# illumi-motherboard.net
KiCad netlist of a schematic drawn in EAGLE
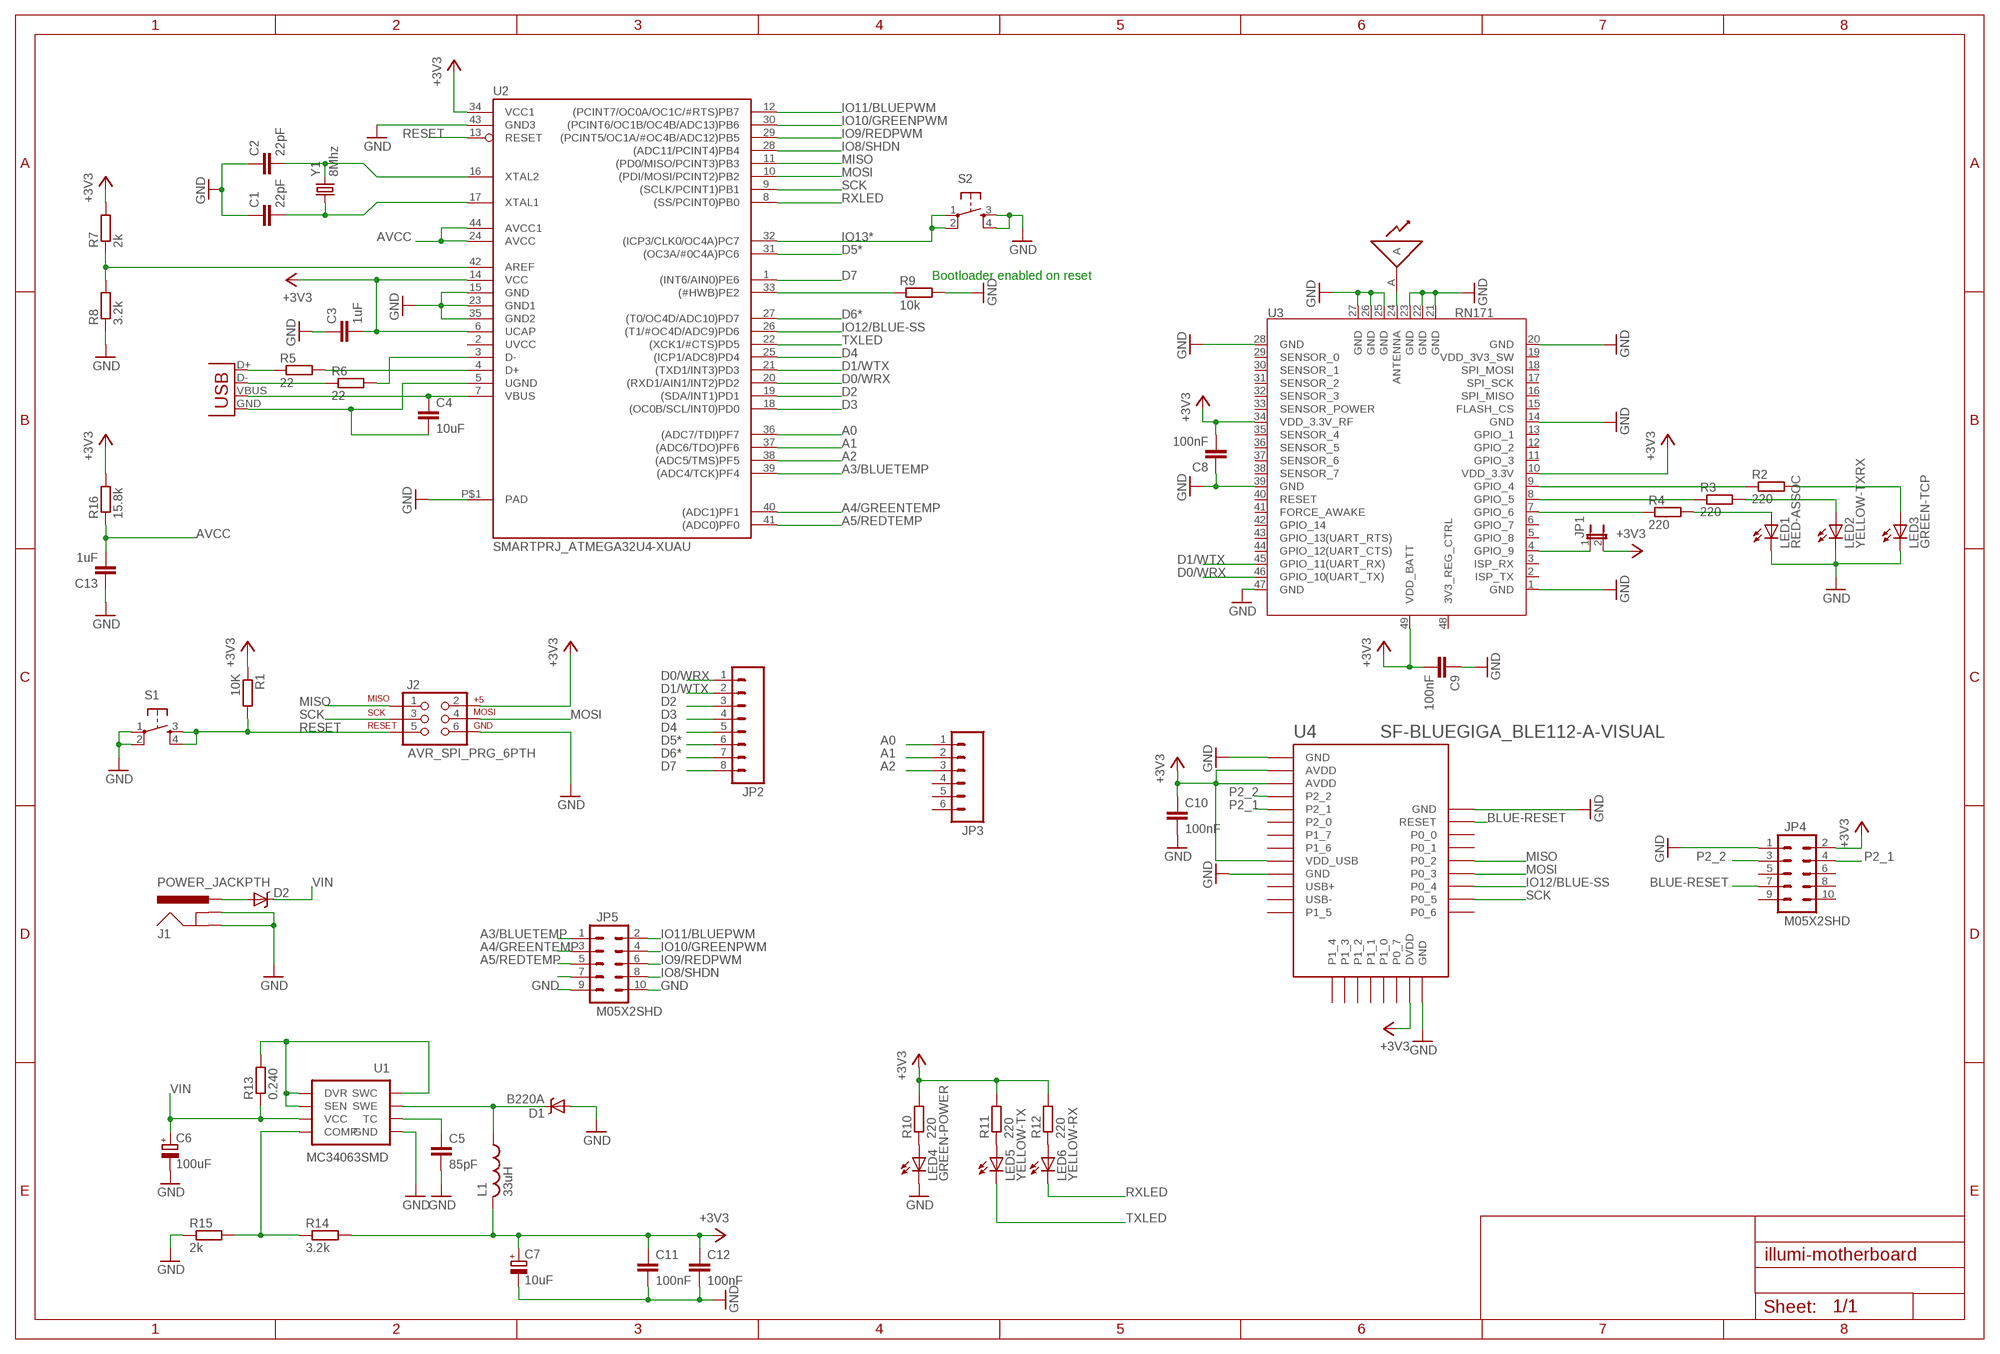
[diagram p0: schematic, sheet 1]

(export (version "E")
  (design (tool "Eeschema 10.0.6"))
  (components
    (comp (ref "A1")
      (value "ANTENNAWIRE")
      (footprint "eagle-import:ANTENNA-WIRE")
      (libsource (lib "eagle-import") (part "ANTENNAWIRE"))
    )
    (comp (ref "C1")
      (value "22pF")
      (footprint "eagle-import:C0805")
      (libsource (lib "eagle-import") (part "C-EUC0805"))
    )
    (comp (ref "C2")
      (value "22pF")
      (footprint "eagle-import:C0805")
      (libsource (lib "eagle-import") (part "C-EUC0805"))
    )
    (comp (ref "C3")
      (value "1uF")
      (footprint "eagle-import:C0805")
      (libsource (lib "eagle-import") (part "C-EUC0805"))
    )
    (comp (ref "C4")
      (value "10uF")
      (footprint "eagle-import:C0805")
      (libsource (lib "eagle-import") (part "C-EUC0805"))
    )
    (comp (ref "C5")
      (value "85pF")
      (footprint "eagle-import:C0805")
      (libsource (lib "eagle-import") (part "C-EUC0805"))
    )
    (comp (ref "C6")
      (value "100uF")
      (footprint "eagle-import:PANASONIC_D")
      (libsource (lib "eagle-import") (part "CPOL-EUD"))
    )
    (comp (ref "C7")
      (value "10uF")
      (footprint "eagle-import:SMC_C")
      (libsource (lib "eagle-import") (part "CPOL-EUSMCC"))
    )
    (comp (ref "C8")
      (value "100nF")
      (footprint "eagle-import:C0805")
      (libsource (lib "eagle-import") (part "C-EUC0805"))
    )
    (comp (ref "C9")
      (value "100nF")
      (footprint "eagle-import:C0805")
      (libsource (lib "eagle-import") (part "C-EUC0805"))
    )
    (comp (ref "C10")
      (value "100nF")
      (footprint "eagle-import:C0805")
      (libsource (lib "eagle-import") (part "C-EUC0805"))
    )
    (comp (ref "C11")
      (value "100nF")
      (footprint "eagle-import:C0805")
      (libsource (lib "eagle-import") (part "C-EUC0805"))
    )
    (comp (ref "C12")
      (value "100nF")
      (footprint "eagle-import:C0805")
      (libsource (lib "eagle-import") (part "C-EUC0805"))
    )
    (comp (ref "C13")
      (value "1uF")
      (footprint "eagle-import:C0805")
      (libsource (lib "eagle-import") (part "C-EUC0805"))
    )
    (comp (ref "D1")
      (value "B220A")
      (footprint "eagle-import:SMA-DIODE-BIG")
      (libsource (lib "eagle-import") (part "DIODE-SCHOTTKYBIGPAD"))
    )
    (comp (ref "D2")
      (value "DIODE-SCHOTTKYBIGPAD")
      (footprint "eagle-import:SMA-DIODE-BIG")
      (libsource (lib "eagle-import") (part "DIODE-SCHOTTKYBIGPAD"))
    )
    (comp (ref "J1")
      (value "POWER_JACKPTH")
      (footprint "eagle-import:POWER_JACK_PTH")
      (libsource (lib "eagle-import") (part "POWER_JACKPTH"))
    )
    (comp (ref "J2")
      (value "AVR_SPI_PRG_6PTH")
      (footprint "eagle-import:2X3")
      (libsource (lib "eagle-import") (part "AVR_SPI_PRG_6PTH"))
    )
    (comp (ref "JP1")
      (value "JUMPER-2PTH")
      (footprint "eagle-import:1X02")
      (libsource (lib "eagle-import") (part "JUMPER-2PTH"))
    )
    (comp (ref "JP2")
      (value "M081X08")
      (footprint "eagle-import:1X08")
      (libsource (lib "eagle-import") (part "M081X08"))
    )
    (comp (ref "JP3")
      (value "M06FEMALE_LOCK")
      (footprint "eagle-import:1X06_FEMALE_LOCK.010")
      (libsource (lib "eagle-import") (part "M06FEMALE_LOCK"))
    )
    (comp (ref "JP4")
      (value "M05X2SHD")
      (footprint "eagle-import:2X5-SHROUDED")
      (libsource (lib "eagle-import") (part "M05X2SHD"))
    )
    (comp (ref "JP5")
      (value "M05X2SHD")
      (footprint "eagle-import:2X5-SHROUDED")
      (libsource (lib "eagle-import") (part "M05X2SHD"))
    )
    (comp (ref "L1")
      (value "33uH")
      (footprint "eagle-import:BOURNS-6045")
      (libsource (lib "eagle-import") (part "L-USBOURNS-6045"))
    )
    (comp (ref "LED1")
      (value "RED-ASSOC")
      (footprint "eagle-import:SML0805")
      (libsource (lib "eagle-import") (part "LEDSML0805"))
    )
    (comp (ref "LED2")
      (value "YELLOW-TXRX")
      (footprint "eagle-import:SML0805")
      (libsource (lib "eagle-import") (part "LEDSML0805"))
    )
    (comp (ref "LED3")
      (value "GREEN-TCP")
      (footprint "eagle-import:SML0805")
      (libsource (lib "eagle-import") (part "LEDSML0805"))
    )
    (comp (ref "LED4")
      (value "GREEN-POWER")
      (footprint "eagle-import:SML0805")
      (libsource (lib "eagle-import") (part "LEDSML0805"))
    )
    (comp (ref "LED5")
      (value "YELLOW-TX")
      (footprint "eagle-import:SML0805")
      (libsource (lib "eagle-import") (part "LEDSML0805"))
    )
    (comp (ref "LED6")
      (value "YELLOW-RX")
      (footprint "eagle-import:SML0805")
      (libsource (lib "eagle-import") (part "LEDSML0805"))
    )
    (comp (ref "R1")
      (value "10K")
      (footprint "eagle-import:R0805")
      (libsource (lib "eagle-import") (part "R-EU_R0805"))
    )
    (comp (ref "R2")
      (value "220")
      (footprint "eagle-import:R0805")
      (libsource (lib "eagle-import") (part "R-EU_R0805"))
    )
    (comp (ref "R3")
      (value "220")
      (footprint "eagle-import:R0805")
      (libsource (lib "eagle-import") (part "R-EU_R0805"))
    )
    (comp (ref "R4")
      (value "220")
      (footprint "eagle-import:R0805")
      (libsource (lib "eagle-import") (part "R-EU_R0805"))
    )
    (comp (ref "R5")
      (value "22")
      (footprint "eagle-import:R0805")
      (libsource (lib "eagle-import") (part "R-EU_R0805"))
    )
    (comp (ref "R6")
      (value "22")
      (footprint "eagle-import:R0805")
      (libsource (lib "eagle-import") (part "R-EU_R0805"))
    )
    (comp (ref "R7")
      (value "2k")
      (footprint "eagle-import:R0805")
      (libsource (lib "eagle-import") (part "R-EU_R0805"))
    )
    (comp (ref "R8")
      (value "3.2k")
      (footprint "eagle-import:R0805")
      (libsource (lib "eagle-import") (part "R-EU_R0805"))
    )
    (comp (ref "R9")
      (value "10k")
      (footprint "eagle-import:R0805")
      (libsource (lib "eagle-import") (part "resistor_R-EU_R0805"))
    )
    (comp (ref "R10")
      (value "220")
      (footprint "eagle-import:R0805")
      (libsource (lib "eagle-import") (part "R-EU_R0805"))
    )
    (comp (ref "R11")
      (value "220")
      (footprint "eagle-import:R0805")
      (libsource (lib "eagle-import") (part "R-EU_R0805"))
    )
    (comp (ref "R12")
      (value "220")
      (footprint "eagle-import:R0805")
      (libsource (lib "eagle-import") (part "R-EU_R0805"))
    )
    (comp (ref "R13")
      (value "0.240")
      (footprint "eagle-import:R1206")
      (libsource (lib "eagle-import") (part "R-EU_R1206"))
    )
    (comp (ref "R14")
      (value "3.2k")
      (footprint "eagle-import:R0805")
      (libsource (lib "eagle-import") (part "R-EU_R0805"))
    )
    (comp (ref "R15")
      (value "2k")
      (footprint "eagle-import:R0805")
      (libsource (lib "eagle-import") (part "R-EU_R0805"))
    )
    (comp (ref "R16")
      (value "15.8k")
      (footprint "eagle-import:R0805")
      (libsource (lib "eagle-import") (part "resistor_R-EU_R0805"))
    )
    (comp (ref "S1")
      (value "TAC_SWITCHB3FS")
      (footprint "eagle-import:OMRON-B3FS")
      (libsource (lib "eagle-import") (part "TAC_SWITCHB3FS"))
    )
    (comp (ref "S2")
      (value "TAC_SWITCHB3FS")
      (footprint "eagle-import:OMRON-B3FS")
      (libsource (lib "eagle-import") (part "TAC_SWITCHB3FS"))
    )
    (comp (ref "U1")
      (value "MC34063SMD")
      (footprint "eagle-import:SO08")
      (libsource (lib "eagle-import") (part "MC34063SMD"))
    )
    (comp (ref "U2")
      (value "SMARTPRJ_ATMEGA32U4-XUAU")
      (footprint "eagle-import:SMARTPRJ_TQFP44-PAD")
      (libsource (lib "eagle-import") (part "SMARTPRJ_ATMEGA32U4-XUAU"))
    )
    (comp (ref "U3")
      (value "RN171")
      (footprint "eagle-import:MODULE_49P-1.27-26.67X17.78")
      (libsource (lib "eagle-import") (part "MODULE_WIFI-RN-171"))
    )
    (comp (ref "U4")
      (value "SF-BLUEGIGA_BLE112-A-VISUAL")
      (footprint "eagle-import:SF-BLUEGIGA_BLE112-A")
      (libsource (lib "eagle-import") (part "SF-BLUEGIGA_BLE112-A-VISUAL"))
    )
    (comp (ref "X1")
      (value "USB-MICROB")
      (footprint "eagle-import:USB-MICROB")
      (libsource (lib "eagle-import") (part "USB-MICROB"))
    )
    (comp (ref "Y1")
      (value "8Mhz")
      (footprint "eagle-import:HC49US")
      (libsource (lib "eagle-import") (part "CRYSTALHC49US"))
    )
  )
  (nets
    (net (code "1") (name "+3V3") (class "Default")
      (node (ref "C10") (pin "1") (pinfunction "1_1") (pintype "passive"))
      (node (ref "C11") (pin "1") (pinfunction "1_1") (pintype "passive"))
      (node (ref "C12") (pin "1") (pinfunction "1_1") (pintype "passive"))
      (node (ref "C3") (pin "2") (pinfunction "2_2") (pintype "passive"))
      (node (ref "C7") (pin "+") (pinfunction "+_+") (pintype "passive"))
      (node (ref "C8") (pin "2") (pinfunction "2_2") (pintype "passive"))
      (node (ref "C9") (pin "2") (pinfunction "2_2") (pintype "passive"))
      (node (ref "J2") (pin "2") (pinfunction "2_2") (pintype "passive"))
      (node (ref "JP1") (pin "2") (pinfunction "2_2") (pintype "passive"))
      (node (ref "JP4") (pin "2") (pinfunction "2_2") (pintype "passive"))
      (node (ref "L1") (pin "P$2") (pinfunction "2_P$2") (pintype "passive"))
      (node (ref "R1") (pin "1") (pinfunction "1_1") (pintype "passive"))
      (node (ref "R10") (pin "2") (pinfunction "2_2") (pintype "passive"))
      (node (ref "R11") (pin "2") (pinfunction "2_2") (pintype "passive"))
      (node (ref "R12") (pin "2") (pinfunction "2_2") (pintype "passive"))
      (node (ref "R14") (pin "2") (pinfunction "2_2") (pintype "passive"))
      (node (ref "R16") (pin "2") (pinfunction "2_2") (pintype "passive"))
      (node (ref "R7") (pin "2") (pinfunction "2_2") (pintype "passive"))
      (node (ref "U2") (pin "14") (pinfunction "VCC_14") (pintype "power_in"))
      (node (ref "U2") (pin "34") (pinfunction "VCC1_34") (pintype "power_in"))
      (node (ref "U2") (pin "6") (pinfunction "UCAP_6") (pintype "passive"))
      (node (ref "U3") (pin "10") (pinfunction "VDD_3.3V_10") (pintype "power_in"))
      (node (ref "U3") (pin "34") (pinfunction "VDD_3.3V_RF_34") (pintype "power_in"))
      (node (ref "U3") (pin "49") (pinfunction "VDD_BATT_49") (pintype "bidirectional"))
      (node (ref "U4") (pin "AVDD1") (pinfunction "AVDD_AVDD1") (pintype "power_in"))
      (node (ref "U4") (pin "AVDD2") (pinfunction "AVDD_AVDD2") (pintype "power_in"))
      (node (ref "U4") (pin "DVDD") (pinfunction "DVDD_DVDD") (pintype "power_in"))
      (node (ref "U4") (pin "VDD_USB") (pinfunction "VDD_USB_VDD_USB") (pintype "power_in"))
    )
    (net (code "2") (name "/A0") (class "Default")
      (node (ref "JP3") (pin "1") (pinfunction "1_1") (pintype "passive"))
      (node (ref "U2") (pin "36") (pinfunction "(ADC7/TDI)PF7_36") (pintype "bidirectional"))
    )
    (net (code "3") (name "/A1") (class "Default")
      (node (ref "JP3") (pin "2") (pinfunction "2_2") (pintype "passive"))
      (node (ref "U2") (pin "37") (pinfunction "(ADC6/TDO)PF6_37") (pintype "bidirectional"))
    )
    (net (code "4") (name "/A2") (class "Default")
      (node (ref "JP3") (pin "3") (pinfunction "3_3") (pintype "passive"))
      (node (ref "U2") (pin "38") (pinfunction "(ADC5/TMS)PF5_38") (pintype "bidirectional"))
    )
    (net (code "5") (name "/A3{slash}BLUETEMP") (class "Default")
      (node (ref "JP5") (pin "1") (pinfunction "1_1") (pintype "passive"))
      (node (ref "U2") (pin "39") (pinfunction "(ADC4/TCK)PF4_39") (pintype "bidirectional"))
    )
    (net (code "6") (name "/A4{slash}GREENTEMP") (class "Default")
      (node (ref "JP5") (pin "3") (pinfunction "3_3") (pintype "passive"))
      (node (ref "U2") (pin "40") (pinfunction "(ADC1)PF1_40") (pintype "bidirectional"))
    )
    (net (code "7") (name "/A5{slash}REDTEMP") (class "Default")
      (node (ref "JP5") (pin "5") (pinfunction "5_5") (pintype "passive"))
      (node (ref "U2") (pin "41") (pinfunction "(ADC0)PF0_41") (pintype "bidirectional"))
    )
    (net (code "8") (name "/AVCC") (class "Default")
      (node (ref "C13") (pin "2") (pinfunction "2_2") (pintype "passive"))
      (node (ref "R16") (pin "1") (pinfunction "1_1") (pintype "passive"))
      (node (ref "U2") (pin "24") (pinfunction "AVCC_24") (pintype "power_in"))
      (node (ref "U2") (pin "44") (pinfunction "AVCC1_44") (pintype "power_in"))
    )
    (net (code "9") (name "/BLUE-RESET") (class "Default")
      (node (ref "JP4") (pin "7") (pinfunction "7_7") (pintype "passive"))
      (node (ref "U4") (pin "RESET") (pinfunction "RESET_RESET") (pintype "input"))
    )
    (net (code "10") (name "/D0{slash}WRX") (class "Default")
      (node (ref "JP2") (pin "1") (pinfunction "1_1") (pintype "passive"))
      (node (ref "U2") (pin "20") (pinfunction "(RXD1/AIN1/INT2)PD2_20") (pintype "bidirectional"))
      (node (ref "U3") (pin "46") (pinfunction "GPIO_10(UART_TX)_46") (pintype "bidirectional"))
    )
    (net (code "11") (name "/D1{slash}WTX") (class "Default")
      (node (ref "JP2") (pin "2") (pinfunction "2_2") (pintype "passive"))
      (node (ref "U2") (pin "21") (pinfunction "(TXD1/INT3)PD3_21") (pintype "bidirectional"))
      (node (ref "U3") (pin "45") (pinfunction "GPIO_11(UART_RX)_45") (pintype "bidirectional"))
    )
    (net (code "12") (name "/D2") (class "Default")
      (node (ref "JP2") (pin "3") (pinfunction "3_3") (pintype "passive"))
      (node (ref "U2") (pin "19") (pinfunction "(SDA/INT1)PD1_19") (pintype "bidirectional"))
    )
    (net (code "13") (name "/D3") (class "Default")
      (node (ref "JP2") (pin "4") (pinfunction "4_4") (pintype "passive"))
      (node (ref "U2") (pin "18") (pinfunction "(OC0B/SCL/INT0)PD0_18") (pintype "bidirectional"))
    )
    (net (code "14") (name "/D4") (class "Default")
      (node (ref "JP2") (pin "5") (pinfunction "5_5") (pintype "passive"))
      (node (ref "U2") (pin "25") (pinfunction "(ICP1/ADC8)PD4_25") (pintype "bidirectional"))
    )
    (net (code "15") (name "/D5*") (class "Default")
      (node (ref "JP2") (pin "6") (pinfunction "6_6") (pintype "passive"))
      (node (ref "U2") (pin "31") (pinfunction "(OC3A/#0C4A)PC6_31") (pintype "bidirectional"))
    )
    (net (code "16") (name "/D6*") (class "Default")
      (node (ref "JP2") (pin "7") (pinfunction "7_7") (pintype "passive"))
      (node (ref "U2") (pin "27") (pinfunction "(T0/OC4D/ADC10)PD7_27") (pintype "bidirectional"))
    )
    (net (code "17") (name "/D7") (class "Default")
      (node (ref "JP2") (pin "8") (pinfunction "8_8") (pintype "passive"))
      (node (ref "U2") (pin "1") (pinfunction "(INT6/AIN0)PE6_1") (pintype "bidirectional"))
    )
    (net (code "18") (name "/IO8{slash}SHDN") (class "Default")
      (node (ref "JP5") (pin "8") (pinfunction "8_8") (pintype "passive"))
      (node (ref "U2") (pin "28") (pinfunction "(ADC11/PCINT4)PB4_28") (pintype "bidirectional"))
    )
    (net (code "19") (name "/IO9{slash}REDPWM") (class "Default")
      (node (ref "JP5") (pin "6") (pinfunction "6_6") (pintype "passive"))
      (node (ref "U2") (pin "29") (pinfunction "(PCINT5/OC1A/#OC4B/ADC12)PB5_29") (pintype "bidirectional"))
    )
    (net (code "20") (name "/IO10{slash}GREENPWM") (class "Default")
      (node (ref "JP5") (pin "4") (pinfunction "4_4") (pintype "passive"))
      (node (ref "U2") (pin "30") (pinfunction "(PCINT6/OC1B/OC4B/ADC13)PB6_30") (pintype "bidirectional"))
    )
    (net (code "21") (name "/IO11{slash}BLUEPWM") (class "Default")
      (node (ref "JP5") (pin "2") (pinfunction "2_2") (pintype "passive"))
      (node (ref "U2") (pin "12") (pinfunction "(PCINT7/OC0A/OC1C/#RTS)PB7_12") (pintype "bidirectional"))
    )
    (net (code "22") (name "/IO12{slash}BLUE-SS") (class "Default")
      (node (ref "U2") (pin "26") (pinfunction "(T1/#OC4D/ADC9)PD6_26") (pintype "bidirectional"))
      (node (ref "U4") (pin "P0_4") (pinfunction "P0_4_P0_4") (pintype "bidirectional"))
    )
    (net (code "23") (name "/IO13*") (class "Default")
      (node (ref "S2") (pin "1") (pinfunction "1_1") (pintype "passive"))
      (node (ref "S2") (pin "2") (pinfunction "2_2") (pintype "passive"))
      (node (ref "U2") (pin "32") (pinfunction "(ICP3/CLK0/OC4A)PC7_32") (pintype "bidirectional"))
    )
    (net (code "24") (name "/MISO") (class "Default")
      (node (ref "J2") (pin "1") (pinfunction "1_1") (pintype "passive"))
      (node (ref "U2") (pin "11") (pinfunction "(PD0/MISO/PCINT3)PB3_11") (pintype "bidirectional"))
      (node (ref "U4") (pin "P0_2") (pinfunction "P0_2_P0_2") (pintype "bidirectional"))
    )
    (net (code "25") (name "/MOSI") (class "Default")
      (node (ref "J2") (pin "4") (pinfunction "4_4") (pintype "passive"))
      (node (ref "U2") (pin "10") (pinfunction "(PDI/MOSI/PCINT2)PB2_10") (pintype "bidirectional"))
      (node (ref "U4") (pin "P0_3") (pinfunction "P0_3_P0_3") (pintype "bidirectional"))
    )
    (net (code "26") (name "/P2_1") (class "Default")
      (node (ref "JP4") (pin "4") (pinfunction "4_4") (pintype "passive"))
      (node (ref "U4") (pin "P2_1") (pinfunction "P2_1_P2_1") (pintype "bidirectional"))
    )
    (net (code "27") (name "/P2_2") (class "Default")
      (node (ref "JP4") (pin "3") (pinfunction "3_3") (pintype "passive"))
      (node (ref "U4") (pin "P2_2") (pinfunction "P2_2_P2_2") (pintype "bidirectional"))
    )
    (net (code "28") (name "/RESET") (class "Default")
      (node (ref "J2") (pin "5") (pinfunction "5_5") (pintype "passive"))
      (node (ref "R1") (pin "2") (pinfunction "2_2") (pintype "passive"))
      (node (ref "S1") (pin "3") (pinfunction "3_3") (pintype "passive"))
      (node (ref "S1") (pin "4") (pinfunction "4_4") (pintype "passive"))
      (node (ref "U2") (pin "13") (pinfunction "RESET_13") (pintype "input"))
    )
    (net (code "29") (name "/RXLED") (class "Default")
      (node (ref "LED6") (pin "C") (pinfunction "C_C") (pintype "passive"))
      (node (ref "U2") (pin "8") (pinfunction "(SS/PCINT0)PB0_8") (pintype "bidirectional"))
    )
    (net (code "30") (name "/SCK") (class "Default")
      (node (ref "J2") (pin "3") (pinfunction "3_3") (pintype "passive"))
      (node (ref "U2") (pin "9") (pinfunction "(SCLK/PCINT1)PB1_9") (pintype "bidirectional"))
      (node (ref "U4") (pin "P0_5") (pinfunction "P0_5_P0_5") (pintype "bidirectional"))
    )
    (net (code "31") (name "/TXLED") (class "Default")
      (node (ref "LED5") (pin "C") (pinfunction "C_C") (pintype "passive"))
      (node (ref "U2") (pin "22") (pinfunction "(XCK1/#CTS)PD5_22") (pintype "bidirectional"))
    )
    (net (code "32") (name "/UVCC") (class "Default")
      (node (ref "U2") (pin "2") (pinfunction "UVCC_2") (pintype "power_in"))
    )
    (net (code "33") (name "/VIN") (class "Default")
      (node (ref "C6") (pin "+") (pinfunction "+_+") (pintype "passive"))
      (node (ref "D2") (pin "C") (pinfunction "C_C") (pintype "passive"))
      (node (ref "R13") (pin "1") (pinfunction "1_1") (pintype "passive"))
      (node (ref "U1") (pin "6") (pinfunction "VCC_6") (pintype "bidirectional"))
    )
    (net (code "34") (name "GND") (class "Default")
      (node (ref "C1") (pin "1") (pinfunction "1_1") (pintype "passive"))
      (node (ref "C10") (pin "2") (pinfunction "2_2") (pintype "passive"))
      (node (ref "C11") (pin "2") (pinfunction "2_2") (pintype "passive"))
      (node (ref "C12") (pin "2") (pinfunction "2_2") (pintype "passive"))
      (node (ref "C13") (pin "1") (pinfunction "1_1") (pintype "passive"))
      (node (ref "C2") (pin "1") (pinfunction "1_1") (pintype "passive"))
      (node (ref "C3") (pin "1") (pinfunction "1_1") (pintype "passive"))
      (node (ref "C5") (pin "2") (pinfunction "2_2") (pintype "passive"))
      (node (ref "C6") (pin "-") (pinfunction "-_-") (pintype "passive"))
      (node (ref "C7") (pin "-") (pinfunction "-_-") (pintype "passive"))
      (node (ref "C8") (pin "1") (pinfunction "1_1") (pintype "passive"))
      (node (ref "C9") (pin "1") (pinfunction "1_1") (pintype "passive"))
      (node (ref "D1") (pin "A") (pinfunction "A_A") (pintype "passive"))
      (node (ref "J1") (pin "GND") (pinfunction "GND_GND") (pintype "bidirectional"))
      (node (ref "J1") (pin "GNDBREAK") (pinfunction "GNDBREAK_GNDBREAK") (pintype "bidirectional"))
      (node (ref "J2") (pin "6") (pinfunction "6_6") (pintype "passive"))
      (node (ref "JP4") (pin "1") (pinfunction "1_1") (pintype "passive"))
      (node (ref "JP5") (pin "10") (pinfunction "10_10") (pintype "passive"))
      (node (ref "JP5") (pin "9") (pinfunction "9_9") (pintype "passive"))
      (node (ref "LED1") (pin "C") (pinfunction "C_C") (pintype "passive"))
      (node (ref "LED2") (pin "C") (pinfunction "C_C") (pintype "passive"))
      (node (ref "LED3") (pin "C") (pinfunction "C_C") (pintype "passive"))
      (node (ref "LED4") (pin "C") (pinfunction "C_C") (pintype "passive"))
      (node (ref "R15") (pin "1") (pinfunction "1_1") (pintype "passive"))
      (node (ref "R8") (pin "1") (pinfunction "1_1") (pintype "passive"))
      (node (ref "R9") (pin "2") (pinfunction "2_2") (pintype "passive"))
      (node (ref "S1") (pin "1") (pinfunction "1_1") (pintype "passive"))
      (node (ref "S1") (pin "2") (pinfunction "2_2") (pintype "passive"))
      (node (ref "S2") (pin "3") (pinfunction "3_3") (pintype "passive"))
      (node (ref "S2") (pin "4") (pinfunction "4_4") (pintype "passive"))
      (node (ref "U1") (pin "4") (pinfunction "GND_4") (pintype "bidirectional"))
      (node (ref "U2") (pin "15") (pinfunction "GND_15") (pintype "power_in"))
      (node (ref "U2") (pin "23") (pinfunction "GND1_23") (pintype "power_in"))
      (node (ref "U2") (pin "35") (pinfunction "GND2_35") (pintype "power_in"))
      (node (ref "U2") (pin "43") (pinfunction "GND3_43") (pintype "power_in"))
      (node (ref "U2") (pin "P$1") (pinfunction "PAD_P$1") (pintype "power_in"))
      (node (ref "U3") (pin "1") (pinfunction "GND_1") (pintype "power_in"))
      (node (ref "U3") (pin "14") (pinfunction "GND_14") (pintype "power_in"))
      (node (ref "U3") (pin "20") (pinfunction "GND_20") (pintype "power_in"))
      (node (ref "U3") (pin "21") (pinfunction "GND_21") (pintype "power_in"))
      (node (ref "U3") (pin "22") (pinfunction "GND_22") (pintype "power_in"))
      (node (ref "U3") (pin "23") (pinfunction "GND_23") (pintype "power_in"))
      (node (ref "U3") (pin "25") (pinfunction "GND_25") (pintype "power_in"))
      (node (ref "U3") (pin "26") (pinfunction "GND_26") (pintype "power_in"))
      (node (ref "U3") (pin "27") (pinfunction "GND_27") (pintype "power_in"))
      (node (ref "U3") (pin "28") (pinfunction "GND_28") (pintype "power_in"))
      (node (ref "U3") (pin "39") (pinfunction "GND_39") (pintype "power_in"))
      (node (ref "U3") (pin "47") (pinfunction "GND_47") (pintype "power_in"))
      (node (ref "U4") (pin "GND1") (pinfunction "GND_GND1") (pintype "power_in"))
      (node (ref "U4") (pin "GND2") (pinfunction "GND_GND2") (pintype "power_in"))
      (node (ref "U4") (pin "GND3") (pinfunction "GND_GND3") (pintype "power_in"))
      (node (ref "U4") (pin "GND4") (pinfunction "GND_GND4") (pintype "power_in"))
    )
    (net (code "35") (name "Net-(D2-PadA)") (class "Default")
      (node (ref "D2") (pin "A") (pinfunction "A_A") (pintype "passive"))
      (node (ref "J1") (pin "PWR") (pinfunction "PWR_PWR") (pintype "bidirectional"))
    )
    (net (code "36") (name "Net-(L1-1)") (class "Default")
      (node (ref "D1") (pin "C") (pinfunction "C_C") (pintype "passive"))
      (node (ref "L1") (pin "P$1") (pinfunction "1_P$1") (pintype "passive"))
      (node (ref "U1") (pin "2") (pinfunction "SWE_2") (pintype "bidirectional"))
    )
    (net (code "37") (name "Net-(LED1-PadA)") (class "Default")
      (node (ref "LED1") (pin "A") (pinfunction "A_A") (pintype "passive"))
      (node (ref "R4") (pin "2") (pinfunction "2_2") (pintype "passive"))
    )
    (net (code "38") (name "Net-(LED2-PadA)") (class "Default")
      (node (ref "LED2") (pin "A") (pinfunction "A_A") (pintype "passive"))
      (node (ref "R3") (pin "2") (pinfunction "2_2") (pintype "passive"))
    )
    (net (code "39") (name "Net-(LED3-PadA)") (class "Default")
      (node (ref "LED3") (pin "A") (pinfunction "A_A") (pintype "passive"))
      (node (ref "R2") (pin "2") (pinfunction "2_2") (pintype "passive"))
    )
    (net (code "40") (name "Net-(LED4-PadA)") (class "Default")
      (node (ref "LED4") (pin "A") (pinfunction "A_A") (pintype "passive"))
      (node (ref "R10") (pin "1") (pinfunction "1_1") (pintype "passive"))
    )
    (net (code "41") (name "Net-(LED5-PadA)") (class "Default")
      (node (ref "LED5") (pin "A") (pinfunction "A_A") (pintype "passive"))
      (node (ref "R11") (pin "1") (pinfunction "1_1") (pintype "passive"))
    )
    (net (code "42") (name "Net-(LED6-PadA)") (class "Default")
      (node (ref "LED6") (pin "A") (pinfunction "A_A") (pintype "passive"))
      (node (ref "R12") (pin "1") (pinfunction "1_1") (pintype "passive"))
    )
    (net (code "43") (name "Net-(R5-Pad1)") (class "Default")
      (node (ref "R5") (pin "1") (pinfunction "1_1") (pintype "passive"))
      (node (ref "X1") (pin "D+") (pinfunction "D+_D+") (pintype "bidirectional"))
    )
    (net (code "44") (name "Net-(R6-Pad1)") (class "Default")
      (node (ref "R6") (pin "1") (pinfunction "1_1") (pintype "passive"))
      (node (ref "X1") (pin "D-") (pinfunction "D-_D-") (pintype "bidirectional"))
    )
    (net (code "45") (name "Net-(U1-COMP)") (class "Default")
      (node (ref "R14") (pin "1") (pinfunction "1_1") (pintype "passive"))
      (node (ref "R15") (pin "2") (pinfunction "2_2") (pintype "passive"))
      (node (ref "U1") (pin "5") (pinfunction "COMP_5") (pintype "bidirectional"))
    )
    (net (code "46") (name "Net-(U1-DVR)") (class "Default")
      (node (ref "R13") (pin "2") (pinfunction "2_2") (pintype "passive"))
      (node (ref "U1") (pin "1") (pinfunction "SWC_1") (pintype "bidirectional"))
      (node (ref "U1") (pin "7") (pinfunction "SEN_7") (pintype "bidirectional"))
      (node (ref "U1") (pin "8") (pinfunction "DVR_8") (pintype "bidirectional"))
    )
    (net (code "47") (name "Net-(U1-TC)") (class "Default")
      (node (ref "C5") (pin "1") (pinfunction "1_1") (pintype "passive"))
      (node (ref "U1") (pin "3") (pinfunction "TC_3") (pintype "bidirectional"))
    )
    (net (code "48") (name "Net-(U2-(#HWB)PE2)") (class "Default")
      (node (ref "R9") (pin "1") (pinfunction "1_1") (pintype "passive"))
      (node (ref "U2") (pin "33") (pinfunction "(#HWB)PE2_33") (pintype "bidirectional"))
    )
    (net (code "49") (name "Net-(U2-AREF)") (class "Default")
      (node (ref "R7") (pin "1") (pinfunction "1_1") (pintype "passive"))
      (node (ref "R8") (pin "2") (pinfunction "2_2") (pintype "passive"))
      (node (ref "U2") (pin "42") (pinfunction "AREF_42") (pintype "power_in"))
    )
    (net (code "50") (name "Net-(U2-D+)") (class "Default")
      (node (ref "R5") (pin "2") (pinfunction "2_2") (pintype "passive"))
      (node (ref "U2") (pin "4") (pinfunction "D+_4") (pintype "bidirectional"))
    )
    (net (code "51") (name "Net-(U2-D-)") (class "Default")
      (node (ref "R6") (pin "2") (pinfunction "2_2") (pintype "passive"))
      (node (ref "U2") (pin "3") (pinfunction "D-_3") (pintype "bidirectional"))
    )
    (net (code "52") (name "Net-(U2-UGND)") (class "Default")
      (node (ref "C4") (pin "2") (pinfunction "2_2") (pintype "passive"))
      (node (ref "U2") (pin "5") (pinfunction "UGND_5") (pintype "power_in"))
      (node (ref "X1") (pin "GND") (pinfunction "GND_GND") (pintype "bidirectional"))
    )
    (net (code "53") (name "Net-(U2-VBUS)") (class "Default")
      (node (ref "C4") (pin "1") (pinfunction "1_1") (pintype "passive"))
      (node (ref "U2") (pin "7") (pinfunction "VBUS_7") (pintype "input"))
      (node (ref "X1") (pin "VBUS") (pinfunction "VBUS_VBUS") (pintype "bidirectional"))
    )
    (net (code "54") (name "Net-(U2-XTAL1)") (class "Default")
      (node (ref "C1") (pin "2") (pinfunction "2_2") (pintype "passive"))
      (node (ref "U2") (pin "17") (pinfunction "XTAL1_17") (pintype "bidirectional"))
      (node (ref "Y1") (pin "1") (pinfunction "1_1") (pintype "passive"))
    )
    (net (code "55") (name "Net-(U2-XTAL2)") (class "Default")
      (node (ref "C2") (pin "2") (pinfunction "2_2") (pintype "passive"))
      (node (ref "U2") (pin "16") (pinfunction "XTAL2_16") (pintype "bidirectional"))
      (node (ref "Y1") (pin "2") (pinfunction "2_2") (pintype "passive"))
    )
    (net (code "56") (name "Net-(U3-ANTENNA)") (class "Default")
      (node (ref "A1") (pin "A") (pinfunction "A_A") (pintype "bidirectional"))
      (node (ref "U3") (pin "24") (pinfunction "ANTENNA_24") (pintype "bidirectional"))
    )
    (net (code "57") (name "Net-(U3-GPIO_4)") (class "Default")
      (node (ref "R2") (pin "1") (pinfunction "1_1") (pintype "passive"))
      (node (ref "U3") (pin "9") (pinfunction "GPIO_4_9") (pintype "bidirectional"))
    )
    (net (code "58") (name "Net-(U3-GPIO_5)") (class "Default")
      (node (ref "R3") (pin "1") (pinfunction "1_1") (pintype "passive"))
      (node (ref "U3") (pin "8") (pinfunction "GPIO_5_8") (pintype "bidirectional"))
    )
    (net (code "59") (name "Net-(U3-GPIO_6)") (class "Default")
      (node (ref "R4") (pin "1") (pinfunction "1_1") (pintype "passive"))
      (node (ref "U3") (pin "7") (pinfunction "GPIO_6_7") (pintype "bidirectional"))
    )
    (net (code "60") (name "Net-(U3-GPIO_9)") (class "Default")
      (node (ref "JP1") (pin "1") (pinfunction "1_1") (pintype "passive"))
      (node (ref "U3") (pin "4") (pinfunction "GPIO_9_4") (pintype "bidirectional"))
    )
    (net (code "61") (name "unconnected-(JP3-Pad4)") (class "Default")
      (node (ref "JP3") (pin "4") (pinfunction "4_4") (pintype "passive"))
    )
    (net (code "62") (name "unconnected-(JP3-Pad5)") (class "Default")
      (node (ref "JP3") (pin "5") (pinfunction "5_5") (pintype "passive"))
    )
    (net (code "63") (name "unconnected-(JP3-Pad6)") (class "Default")
      (node (ref "JP3") (pin "6") (pinfunction "6_6") (pintype "passive"))
    )
    (net (code "64") (name "unconnected-(JP4-Pad5)") (class "Default")
      (node (ref "JP4") (pin "5") (pinfunction "5_5") (pintype "passive"))
    )
    (net (code "65") (name "unconnected-(JP4-Pad6)") (class "Default")
      (node (ref "JP4") (pin "6") (pinfunction "6_6") (pintype "passive"))
    )
    (net (code "66") (name "unconnected-(JP4-Pad8)") (class "Default")
      (node (ref "JP4") (pin "8") (pinfunction "8_8") (pintype "passive"))
    )
    (net (code "67") (name "unconnected-(JP4-Pad9)") (class "Default")
      (node (ref "JP4") (pin "9") (pinfunction "9_9") (pintype "passive"))
    )
    (net (code "68") (name "unconnected-(JP4-Pad10)") (class "Default")
      (node (ref "JP4") (pin "10") (pinfunction "10_10") (pintype "passive"))
    )
    (net (code "69") (name "unconnected-(JP5-Pad7)") (class "Default")
      (node (ref "JP5") (pin "7") (pinfunction "7_7") (pintype "passive"))
    )
    (net (code "70") (name "unconnected-(U3-3V3_REG_CTRL-Pad48)") (class "Default")
      (node (ref "U3") (pin "48") (pinfunction "3V3_REG_CTRL_48") (pintype "input"))
    )
    (net (code "71") (name "unconnected-(U3-FLASH_CS-Pad15)") (class "Default")
      (node (ref "U3") (pin "15") (pinfunction "FLASH_CS_15") (pintype "bidirectional"))
    )
    (net (code "72") (name "unconnected-(U3-FORCE_AWAKE-Pad41)") (class "Default")
      (node (ref "U3") (pin "41") (pinfunction "FORCE_AWAKE_41") (pintype "bidirectional"))
    )
    (net (code "73") (name "unconnected-(U3-GPIO_1-Pad13)") (class "Default")
      (node (ref "U3") (pin "13") (pinfunction "GPIO_1_13") (pintype "bidirectional"))
    )
    (net (code "74") (name "unconnected-(U3-GPIO_2-Pad12)") (class "Default")
      (node (ref "U3") (pin "12") (pinfunction "GPIO_2_12") (pintype "bidirectional"))
    )
    (net (code "75") (name "unconnected-(U3-GPIO_3-Pad11)") (class "Default")
      (node (ref "U3") (pin "11") (pinfunction "GPIO_3_11") (pintype "bidirectional"))
    )
    (net (code "76") (name "unconnected-(U3-GPIO_7-Pad6)") (class "Default")
      (node (ref "U3") (pin "6") (pinfunction "GPIO_7_6") (pintype "bidirectional"))
    )
    (net (code "77") (name "unconnected-(U3-GPIO_8-Pad5)") (class "Default")
      (node (ref "U3") (pin "5") (pinfunction "GPIO_8_5") (pintype "bidirectional"))
    )
    (net (code "78") (name "unconnected-(U3-GPIO_12(UART_CTS)-Pad44)") (class "Default")
      (node (ref "U3") (pin "44") (pinfunction "GPIO_12(UART_CTS)_44") (pintype "bidirectional"))
    )
    (net (code "79") (name "unconnected-(U3-GPIO_13(UART_RTS)-Pad43)") (class "Default")
      (node (ref "U3") (pin "43") (pinfunction "GPIO_13(UART_RTS)_43") (pintype "bidirectional"))
    )
    (net (code "80") (name "unconnected-(U3-GPIO_14-Pad42)") (class "Default")
      (node (ref "U3") (pin "42") (pinfunction "GPIO_14_42") (pintype "bidirectional"))
    )
    (net (code "81") (name "unconnected-(U3-ISP_RX-Pad3)") (class "Default")
      (node (ref "U3") (pin "3") (pinfunction "ISP_RX_3") (pintype "bidirectional"))
    )
    (net (code "82") (name "unconnected-(U3-ISP_TX-Pad2)") (class "Default")
      (node (ref "U3") (pin "2") (pinfunction "ISP_TX_2") (pintype "bidirectional"))
    )
    (net (code "83") (name "unconnected-(U3-RESET-Pad40)") (class "Default")
      (node (ref "U3") (pin "40") (pinfunction "RESET_40") (pintype "input"))
    )
    (net (code "84") (name "unconnected-(U3-SENSOR_0-Pad29)") (class "Default")
      (node (ref "U3") (pin "29") (pinfunction "SENSOR_0_29") (pintype "input"))
    )
    (net (code "85") (name "unconnected-(U3-SENSOR_1-Pad30)") (class "Default")
      (node (ref "U3") (pin "30") (pinfunction "SENSOR_1_30") (pintype "input"))
    )
    (net (code "86") (name "unconnected-(U3-SENSOR_2-Pad31)") (class "Default")
      (node (ref "U3") (pin "31") (pinfunction "SENSOR_2_31") (pintype "input"))
    )
    (net (code "87") (name "unconnected-(U3-SENSOR_3-Pad32)") (class "Default")
      (node (ref "U3") (pin "32") (pinfunction "SENSOR_3_32") (pintype "input"))
    )
    (net (code "88") (name "unconnected-(U3-SENSOR_4-Pad35)") (class "Default")
      (node (ref "U3") (pin "35") (pinfunction "SENSOR_4_35") (pintype "input"))
    )
    (net (code "89") (name "unconnected-(U3-SENSOR_5-Pad36)") (class "Default")
      (node (ref "U3") (pin "36") (pinfunction "SENSOR_5_36") (pintype "input"))
    )
    (net (code "90") (name "unconnected-(U3-SENSOR_6-Pad37)") (class "Default")
      (node (ref "U3") (pin "37") (pinfunction "SENSOR_6_37") (pintype "input"))
    )
    (net (code "91") (name "unconnected-(U3-SENSOR_7-Pad38)") (class "Default")
      (node (ref "U3") (pin "38") (pinfunction "SENSOR_7_38") (pintype "input"))
    )
    (net (code "92") (name "unconnected-(U3-SENSOR_POWER-Pad33)") (class "Default")
      (node (ref "U3") (pin "33") (pinfunction "SENSOR_POWER_33") (pintype "output"))
    )
    (net (code "93") (name "unconnected-(U3-SPI_MISO-Pad16)") (class "Default")
      (node (ref "U3") (pin "16") (pinfunction "SPI_MISO_16") (pintype "bidirectional"))
    )
    (net (code "94") (name "unconnected-(U3-SPI_MOSI-Pad18)") (class "Default")
      (node (ref "U3") (pin "18") (pinfunction "SPI_MOSI_18") (pintype "bidirectional"))
    )
    (net (code "95") (name "unconnected-(U3-SPI_SCK-Pad17)") (class "Default")
      (node (ref "U3") (pin "17") (pinfunction "SPI_SCK_17") (pintype "bidirectional"))
    )
    (net (code "96") (name "unconnected-(U3-VDD_3V3_SW-Pad19)") (class "Default")
      (node (ref "U3") (pin "19") (pinfunction "VDD_3V3_SW_19") (pintype "bidirectional"))
    )
    (net (code "97") (name "unconnected-(U4-PadP0_0)") (class "Default")
      (node (ref "U4") (pin "P0_0") (pinfunction "P0_0_P0_0") (pintype "bidirectional"))
    )
    (net (code "98") (name "unconnected-(U4-PadP0_1)") (class "Default")
      (node (ref "U4") (pin "P0_1") (pinfunction "P0_1_P0_1") (pintype "bidirectional"))
    )
    (net (code "99") (name "unconnected-(U4-PadP0_6)") (class "Default")
      (node (ref "U4") (pin "P0_6") (pinfunction "P0_6_P0_6") (pintype "bidirectional"))
    )
    (net (code "100") (name "unconnected-(U4-PadP0_7)") (class "Default")
      (node (ref "U4") (pin "P0_7") (pinfunction "P0_7_P0_7") (pintype "bidirectional"))
    )
    (net (code "101") (name "unconnected-(U4-PadP1_0)") (class "Default")
      (node (ref "U4") (pin "P1_0") (pinfunction "P1_0_P1_0") (pintype "bidirectional"))
    )
    (net (code "102") (name "unconnected-(U4-PadP1_1)") (class "Default")
      (node (ref "U4") (pin "P1_1") (pinfunction "P1_1_P1_1") (pintype "bidirectional"))
    )
    (net (code "103") (name "unconnected-(U4-PadP1_2)") (class "Default")
      (node (ref "U4") (pin "P1_2") (pinfunction "P1_2_P1_2") (pintype "bidirectional"))
    )
    (net (code "104") (name "unconnected-(U4-PadP1_3)") (class "Default")
      (node (ref "U4") (pin "P1_3") (pinfunction "P1_3_P1_3") (pintype "bidirectional"))
    )
    (net (code "105") (name "unconnected-(U4-PadP1_4)") (class "Default")
      (node (ref "U4") (pin "P1_4") (pinfunction "P1_4_P1_4") (pintype "bidirectional"))
    )
    (net (code "106") (name "unconnected-(U4-PadP1_5)") (class "Default")
      (node (ref "U4") (pin "P1_5") (pinfunction "P1_5_P1_5") (pintype "bidirectional"))
    )
    (net (code "107") (name "unconnected-(U4-PadP1_6)") (class "Default")
      (node (ref "U4") (pin "P1_6") (pinfunction "P1_6_P1_6") (pintype "bidirectional"))
    )
    (net (code "108") (name "unconnected-(U4-PadP1_7)") (class "Default")
      (node (ref "U4") (pin "P1_7") (pinfunction "P1_7_P1_7") (pintype "bidirectional"))
    )
    (net (code "109") (name "unconnected-(U4-PadP2_0)") (class "Default")
      (node (ref "U4") (pin "P2_0") (pinfunction "P2_0_P2_0") (pintype "bidirectional"))
    )
    (net (code "110") (name "unconnected-(U4-PadUSB+)") (class "Default")
      (node (ref "U4") (pin "USB+") (pinfunction "USB+_USB+") (pintype "bidirectional"))
    )
    (net (code "111") (name "unconnected-(U4-PadUSB-)") (class "Default")
      (node (ref "U4") (pin "USB-") (pinfunction "USB-_USB-") (pintype "bidirectional"))
    )
  )
)
